# USBCharger.net
KiCad netlist of a schematic drawn in Altium Designer
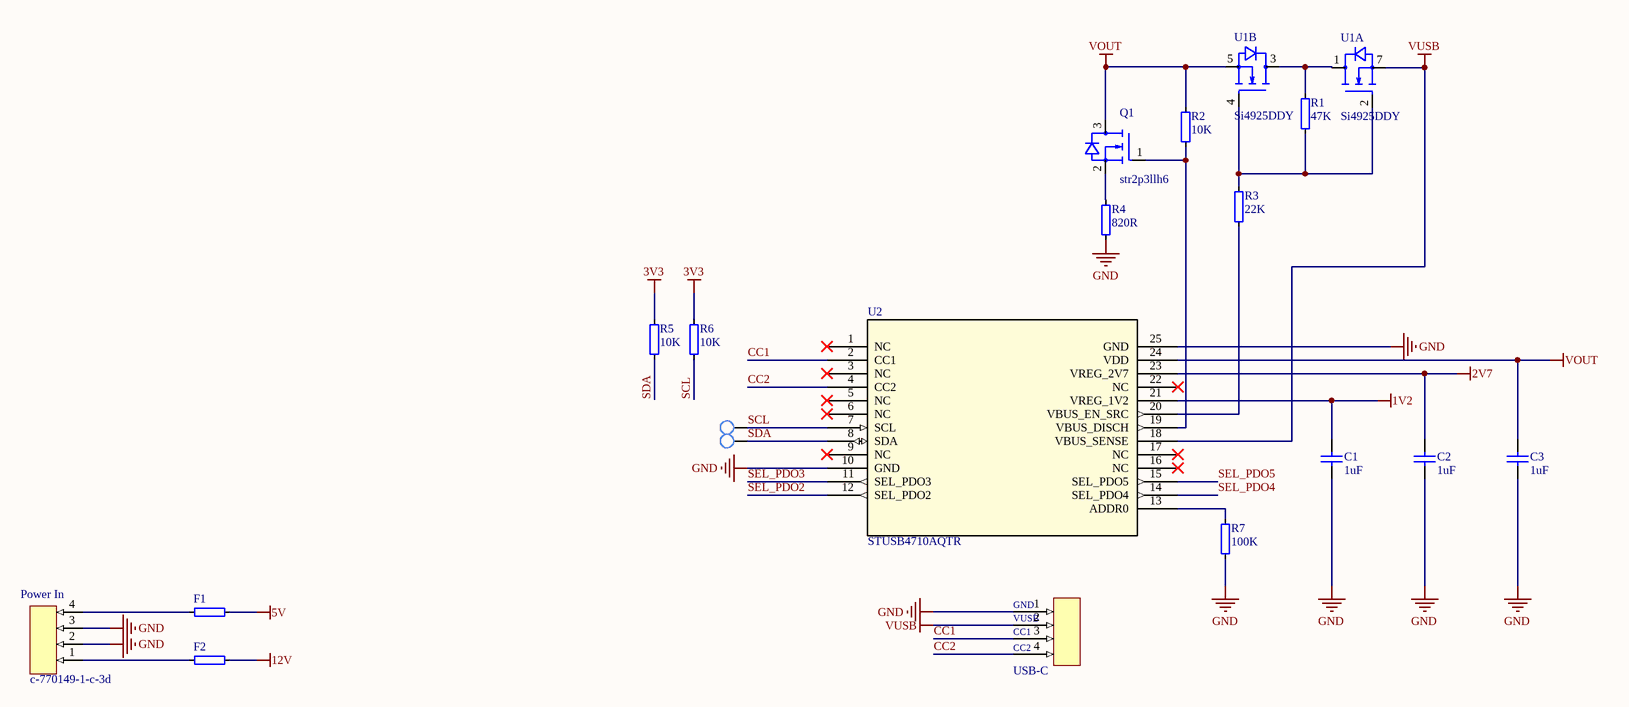
[diagram p0: USBCharger.SchDoc]

(export (version "E")
  (design (tool "Eeschema 10.0.6"))
  (components
    (comp (ref "C1")
      (value "1uF")
      (footprint "C0603")
      (description "Capacitor")
      (fields (field (name "PUBLISHER") "Altium Limited"))
      (libsource (lib "Passives") (part "CAP"))
    )
    (comp (ref "C2")
      (value "1uF")
      (footprint "C0603")
      (description "Capacitor")
      (fields (field (name "PUBLISHER") "Altium Limited"))
      (libsource (lib "Passives") (part "CAP"))
    )
    (comp (ref "C3")
      (value "1uF")
      (footprint "C0603")
      (description "Capacitor")
      (fields (field (name "PUBLISHER") "Altium Limited"))
      (libsource (lib "Passives") (part "CAP"))
    )
    (comp (ref "F1")
      (value "0154010.DR")
      (footprint "0154010.DR")
      (description "Polymeric PTC Resettable Fuse 6V 750mA Ih Surface Mount 1206 (3216 Metric), Concave")
      (fields (field (name "PART NUMBER") "R0201-0R") (field (name "PUBLISHER") "Nordic Semiconductor"))
      (libsource (lib "Passives") (part "Fuse"))
    )
    (comp (ref "F2")
      (value "0154010.DR")
      (footprint "0154010.DR")
      (description "Polymeric PTC Resettable Fuse 6V 750mA Ih Surface Mount 1206 (3216 Metric), Concave")
      (fields (field (name "PART NUMBER") "R0201-0R") (field (name "PUBLISHER") "Nordic Semiconductor"))
      (libsource (lib "Passives") (part "Fuse"))
    )
    (comp (ref "Power In")
      (value "c-770149-1-c-3d")
      (footprint "c-770149-1-c-3d")
      (description "Generic 4 pin connector, see footprint for MPN")
      (libsource (lib "Connector") (part "4 Pin connector"))
    )
    (comp (ref "Q1")
      (value "str2p3llh6")
      (footprint "SOT23-3")
      (description "N-Channel 20V 100mA _Ta_ 150mW _Ta_ Surface Mount VMT3")
      (fields (field (name "MF") "Rohm") (field (name "DIGI-KEY_PART_NUMBER") "RUM001L02T2CLCT-ND"))
      (libsource (lib "MCU") (part "Transistor"))
    )
    (comp (ref "R1")
      (value "47K")
      (footprint "RES0603R")
      (description "Resistor, ±5%, 0.05W")
      (fields (field (name "PART NUMBER") "R0201-0R") (field (name "PUBLISHER") "Nordic Semiconductor"))
      (libsource (lib "Passives") (part "RES"))
    )
    (comp (ref "R2")
      (value "10K")
      (footprint "RES0603R")
      (description "Resistor, ±5%, 0.05W")
      (fields (field (name "PART NUMBER") "R0201-0R") (field (name "PUBLISHER") "Nordic Semiconductor"))
      (libsource (lib "Passives") (part "RES"))
    )
    (comp (ref "R3")
      (value "22K")
      (footprint "RES0603R")
      (description "Resistor, ±5%, 0.05W")
      (fields (field (name "PART NUMBER") "R0201-0R") (field (name "PUBLISHER") "Nordic Semiconductor"))
      (libsource (lib "Passives") (part "RES"))
    )
    (comp (ref "R4")
      (value "820R")
      (footprint "RES1206R")
      (description "Resistor, ±5%, 0.05W")
      (fields (field (name "PART NUMBER") "R0201-0R") (field (name "PUBLISHER") "Nordic Semiconductor"))
      (libsource (lib "Passives") (part "RES"))
    )
    (comp (ref "R5")
      (value "10K")
      (footprint "RES0603R")
      (description "Resistor, ±5%, 0.05W")
      (fields (field (name "PART NUMBER") "R0201-0R") (field (name "PUBLISHER") "Nordic Semiconductor"))
      (libsource (lib "Passives") (part "RES"))
    )
    (comp (ref "R6")
      (value "10K")
      (footprint "RES0603R")
      (description "Resistor, ±5%, 0.05W")
      (fields (field (name "PART NUMBER") "R0201-0R") (field (name "PUBLISHER") "Nordic Semiconductor"))
      (libsource (lib "Passives") (part "RES"))
    )
    (comp (ref "R7")
      (value "100K")
      (footprint "RES0603R")
      (description "Resistor, ±5%, 0.05W")
      (fields (field (name "PART NUMBER") "R0201-0R") (field (name "PUBLISHER") "Nordic Semiconductor"))
      (libsource (lib "Passives") (part "RES"))
    )
    (comp (ref "SCL1") (value "DNP") (footprint "smd tp") (libsource (lib "MISC") (part "TP")))
    (comp (ref "SDA1") (value "DNP") (footprint "smd tp") (libsource (lib "MISC") (part "TP")))
    (comp (ref "U1")
      (value "Si4925DDY")
      (footprint "si4925dd")
      (description "Si4925DDY, dual mosfet")
      (libsource (lib "") (part "Si4925DDY_1"))
    )
    (comp (ref "U2")
      (value "STUSB4710AQTR")
      (footprint "STUSB4710AQTR")
      (description "No Description Available")
      (fields (field (name "COPYRIGHT") "Copyright (C) 2018 Accelerated Designs. All rights reserved"))
      (libsource (lib "MCU") (part "STUSB4710AQTR"))
    )
    (comp (ref "USB-C")
      (value "TYPE-C-31-M-17")
      (footprint "TYPE-C-31-M-17")
      (description "Usb C power connector")
      (libsource (lib "Connector") (part "TYPE-C-31-M-17"))
    )
  )
  (nets
    (net (code "1") (name "/CC1") (class "Default")
      (node (ref "U2") (pin "2") (pinfunction "CC1_2") (pintype "passive"))
      (node (ref "USB-C") (pin "3") (pintype "input"))
    )
    (net (code "2") (name "/CC2") (class "Default")
      (node (ref "U2") (pin "4") (pinfunction "CC2_4") (pintype "passive"))
      (node (ref "USB-C") (pin "4") (pintype "input"))
    )
    (net (code "3") (name "/SCL") (class "Default")
      (node (ref "R6") (pin "1") (pinfunction "1_1") (pintype "passive"))
      (node (ref "SCL1") (pin "1") (pinfunction "1_1") (pintype "passive"))
      (node (ref "U2") (pin "7") (pinfunction "SCL_7") (pintype "input"))
    )
    (net (code "4") (name "/SDA") (class "Default")
      (node (ref "R5") (pin "1") (pinfunction "1_1") (pintype "passive"))
      (node (ref "SDA1") (pin "1") (pinfunction "1_1") (pintype "passive"))
      (node (ref "U2") (pin "8") (pinfunction "SDA_8") (pintype "bidirectional"))
    )
    (net (code "5") (name "/SEL_PDO2") (class "Default")
      (node (ref "U2") (pin "12") (pinfunction "SEL_PDO2_12") (pintype "output"))
    )
    (net (code "6") (name "/SEL_PDO3") (class "Default")
      (node (ref "U2") (pin "11") (pinfunction "SEL_PDO3_11") (pintype "output"))
    )
    (net (code "7") (name "/SEL_PDO4") (class "Default")
      (node (ref "U2") (pin "14") (pinfunction "SEL_PDO4_14") (pintype "output"))
    )
    (net (code "8") (name "/SEL_PDO5") (class "Default")
      (node (ref "U2") (pin "15") (pinfunction "SEL_PDO5_15") (pintype "output"))
    )
    (net (code "9") (name "1V2") (class "Default")
      (node (ref "C1") (pin "2") (pinfunction "2_2") (pintype "passive"))
      (node (ref "U2") (pin "21") (pinfunction "VREG_1V2_21") (pintype "passive"))
    )
    (net (code "10") (name "2V7") (class "Default")
      (node (ref "C2") (pin "2") (pinfunction "2_2") (pintype "passive"))
      (node (ref "U2") (pin "23") (pinfunction "VREG_2V7_23") (pintype "passive"))
    )
    (net (code "11") (name "3V3") (class "Default")
      (node (ref "R5") (pin "2") (pinfunction "2_2") (pintype "passive"))
      (node (ref "R6") (pin "2") (pinfunction "2_2") (pintype "passive"))
    )
    (net (code "12") (name "5V") (class "Default")
      (node (ref "F1") (pin "2") (pinfunction "2_2") (pintype "passive"))
    )
    (net (code "13") (name "12V") (class "Default")
      (node (ref "F2") (pin "2") (pinfunction "2_2") (pintype "passive"))
    )
    (net (code "14") (name "GND") (class "Default")
      (node (ref "C1") (pin "1") (pinfunction "1_1") (pintype "passive"))
      (node (ref "C2") (pin "1") (pinfunction "1_1") (pintype "passive"))
      (node (ref "C3") (pin "1") (pinfunction "1_1") (pintype "passive"))
      (node (ref "Power In") (pin "2") (pintype "input"))
      (node (ref "Power In") (pin "3") (pintype "input"))
      (node (ref "R4") (pin "1") (pinfunction "1_1") (pintype "passive"))
      (node (ref "R7") (pin "1") (pinfunction "1_1") (pintype "passive"))
      (node (ref "U2") (pin "10") (pinfunction "GND_10") (pintype "passive"))
      (node (ref "U2") (pin "25") (pinfunction "GND_25") (pintype "passive"))
      (node (ref "USB-C") (pin "1") (pintype "input"))
    )
    (net (code "15") (name "Net-(F1-Pad1)") (class "Default")
      (node (ref "F1") (pin "1") (pinfunction "1_1") (pintype "passive"))
      (node (ref "Power In") (pin "4") (pintype "input"))
    )
    (net (code "16") (name "Net-(F2-Pad1)") (class "Default")
      (node (ref "F2") (pin "1") (pinfunction "1_1") (pintype "passive"))
      (node (ref "Power In") (pin "1") (pintype "input"))
    )
    (net (code "17") (name "Net-(Q1-G)") (class "Default")
      (node (ref "Q1") (pin "1") (pinfunction "G_1") (pintype "passive"))
      (node (ref "R2") (pin "1") (pinfunction "1_1") (pintype "passive"))
      (node (ref "U2") (pin "19") (pinfunction "VBUS_DISCH_19") (pintype "output"))
    )
    (net (code "18") (name "Net-(Q1-S)") (class "Default")
      (node (ref "Q1") (pin "2") (pinfunction "S_2") (pintype "passive"))
      (node (ref "R4") (pin "2") (pinfunction "2_2") (pintype "passive"))
    )
    (net (code "19") (name "Net-(U1A-D)") (class "Default")
      (node (ref "R1") (pin "2") (pinfunction "2_2") (pintype "passive"))
      (node (ref "U1") (pin "1") (pinfunction "D_1") (pintype "passive"))
      (node (ref "U1") (pin "3") (pinfunction "D_3") (pintype "passive"))
    )
    (net (code "20") (name "Net-(U1A-G)") (class "Default")
      (node (ref "R1") (pin "1") (pinfunction "1_1") (pintype "passive"))
      (node (ref "R3") (pin "2") (pinfunction "2_2") (pintype "passive"))
      (node (ref "U1") (pin "2") (pinfunction "G_2") (pintype "passive"))
      (node (ref "U1") (pin "4") (pinfunction "G_4") (pintype "passive"))
    )
    (net (code "21") (name "Net-(U2-ADDR0)") (class "Default")
      (node (ref "R7") (pin "2") (pinfunction "2_2") (pintype "passive"))
      (node (ref "U2") (pin "13") (pinfunction "ADDR0_13") (pintype "passive"))
    )
    (net (code "22") (name "Net-(U2-VBUS_EN_SRC)") (class "Default")
      (node (ref "R3") (pin "1") (pinfunction "1_1") (pintype "passive"))
      (node (ref "U2") (pin "20") (pinfunction "VBUS_EN_SRC_20") (pintype "output"))
    )
    (net (code "23") (name "VOUT") (class "Default")
      (node (ref "C3") (pin "2") (pinfunction "2_2") (pintype "passive"))
      (node (ref "Q1") (pin "3") (pinfunction "D_3") (pintype "passive"))
      (node (ref "R2") (pin "2") (pinfunction "2_2") (pintype "passive"))
      (node (ref "U1") (pin "5") (pinfunction "S_5") (pintype "passive"))
      (node (ref "U2") (pin "24") (pinfunction "VDD_24") (pintype "power_in"))
    )
    (net (code "24") (name "VUSB") (class "Default")
      (node (ref "U1") (pin "7") (pinfunction "S_7") (pintype "passive"))
      (node (ref "U2") (pin "18") (pinfunction "VBUS_SENSE_18") (pintype "passive"))
      (node (ref "USB-C") (pin "2") (pintype "input"))
    )
    (net (code "25") (name "unconnected-(U2-NC-Pad1)") (class "Default")
      (node (ref "U2") (pin "1") (pinfunction "NC_1") (pintype "passive+no_connect"))
    )
    (net (code "26") (name "unconnected-(U2-NC-Pad3)") (class "Default")
      (node (ref "U2") (pin "3") (pinfunction "NC_3") (pintype "passive+no_connect"))
    )
    (net (code "27") (name "unconnected-(U2-NC-Pad5)") (class "Default")
      (node (ref "U2") (pin "5") (pinfunction "NC_5") (pintype "passive+no_connect"))
    )
    (net (code "28") (name "unconnected-(U2-NC-Pad6)") (class "Default")
      (node (ref "U2") (pin "6") (pinfunction "NC_6") (pintype "passive+no_connect"))
    )
    (net (code "29") (name "unconnected-(U2-NC-Pad9)") (class "Default")
      (node (ref "U2") (pin "9") (pinfunction "NC_9") (pintype "passive+no_connect"))
    )
    (net (code "30") (name "unconnected-(U2-NC-Pad16)") (class "Default")
      (node (ref "U2") (pin "16") (pinfunction "NC_16") (pintype "passive+no_connect"))
    )
    (net (code "31") (name "unconnected-(U2-NC-Pad17)") (class "Default")
      (node (ref "U2") (pin "17") (pinfunction "NC_17") (pintype "passive+no_connect"))
    )
    (net (code "32") (name "unconnected-(U2-NC-Pad22)") (class "Default")
      (node (ref "U2") (pin "22") (pinfunction "NC_22") (pintype "passive+no_connect"))
    )
  )
)
